# IOSEC8.net
KiCad netlist of a schematic drawn in EAGLE
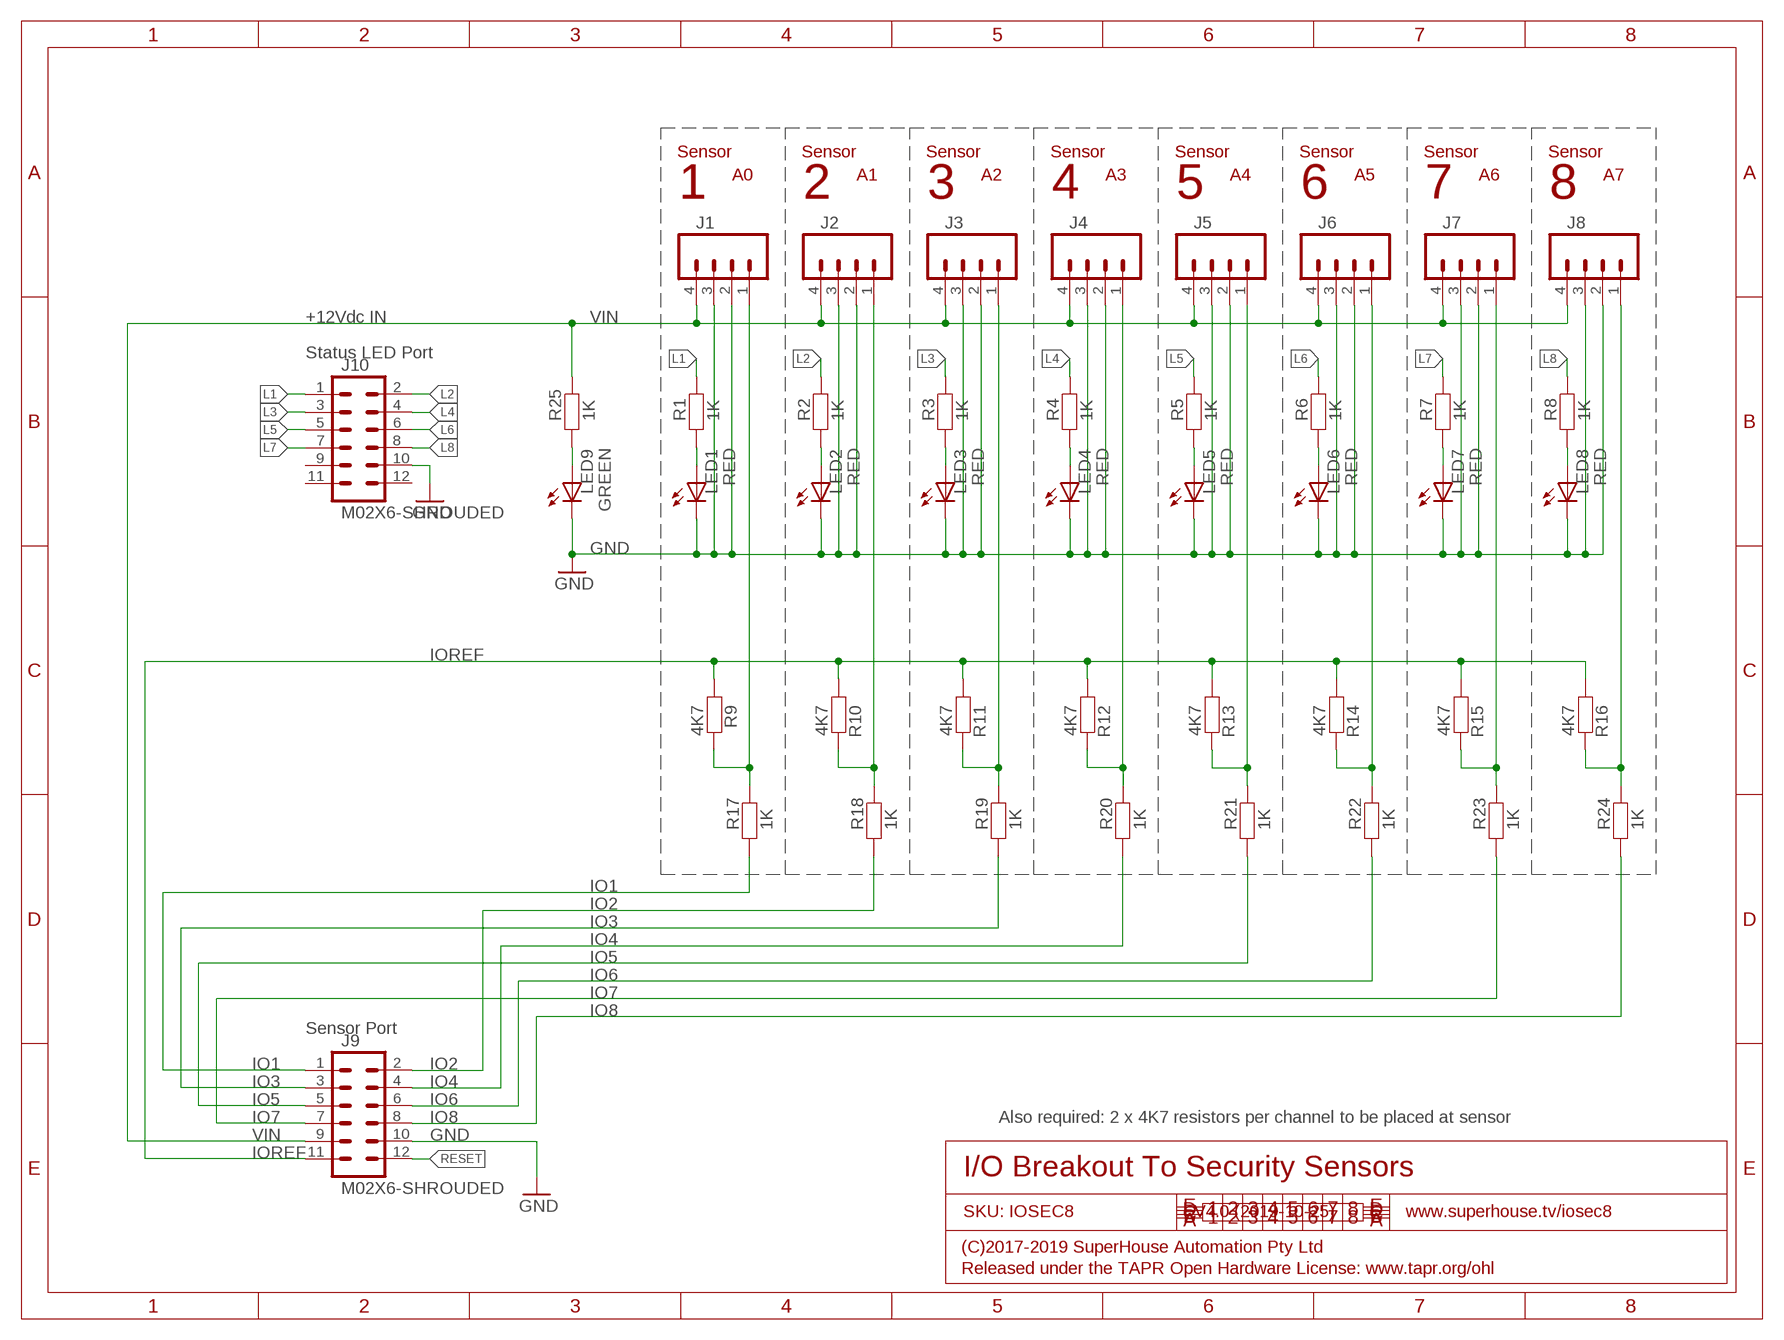
[diagram p0: schematic, sheet 1]

(export (version "E")
  (design (tool "Eeschema 10.0.6"))
  (components
    (comp (ref "J1")
      (value "M04-SCREW-3.5MM")
      (footprint "eagle-import:SCREWTERMINAL-3.5MM-4")
      (libsource (lib "eagle-import") (part "M04-SCREW-3.5MM"))
    )
    (comp (ref "J2")
      (value "M04-SCREW-3.5MM")
      (footprint "eagle-import:SCREWTERMINAL-3.5MM-4")
      (libsource (lib "eagle-import") (part "M04-SCREW-3.5MM"))
    )
    (comp (ref "J3")
      (value "M04-SCREW-3.5MM")
      (footprint "eagle-import:SCREWTERMINAL-3.5MM-4")
      (libsource (lib "eagle-import") (part "M04-SCREW-3.5MM"))
    )
    (comp (ref "J4")
      (value "M04-SCREW-3.5MM")
      (footprint "eagle-import:SCREWTERMINAL-3.5MM-4")
      (libsource (lib "eagle-import") (part "M04-SCREW-3.5MM"))
    )
    (comp (ref "J5")
      (value "M04-SCREW-3.5MM")
      (footprint "eagle-import:SCREWTERMINAL-3.5MM-4")
      (libsource (lib "eagle-import") (part "M04-SCREW-3.5MM"))
    )
    (comp (ref "J6")
      (value "M04-SCREW-3.5MM")
      (footprint "eagle-import:SCREWTERMINAL-3.5MM-4")
      (libsource (lib "eagle-import") (part "M04-SCREW-3.5MM"))
    )
    (comp (ref "J7")
      (value "M04-SCREW-3.5MM")
      (footprint "eagle-import:SCREWTERMINAL-3.5MM-4")
      (libsource (lib "eagle-import") (part "M04-SCREW-3.5MM"))
    )
    (comp (ref "J8")
      (value "M04-SCREW-3.5MM")
      (footprint "eagle-import:SCREWTERMINAL-3.5MM-4")
      (libsource (lib "eagle-import") (part "M04-SCREW-3.5MM"))
    )
    (comp (ref "J9")
      (value "M02X6-SHROUDED")
      (footprint "eagle-import:2X06-SHROUDED")
      (libsource (lib "eagle-import") (part "M02X6-SHROUDED"))
    )
    (comp (ref "J10")
      (value "M02X6-SHROUDED")
      (footprint "eagle-import:2X06-SHROUDED")
      (libsource (lib "eagle-import") (part "M02X6-SHROUDED"))
    )
    (comp (ref "LED1")
      (value "RED")
      (footprint "eagle-import:LED-0603")
      (libsource (lib "eagle-import") (part "LED0603"))
    )
    (comp (ref "LED2")
      (value "RED")
      (footprint "eagle-import:LED-0603")
      (libsource (lib "eagle-import") (part "LED0603"))
    )
    (comp (ref "LED3")
      (value "RED")
      (footprint "eagle-import:LED-0603")
      (libsource (lib "eagle-import") (part "LED0603"))
    )
    (comp (ref "LED4")
      (value "RED")
      (footprint "eagle-import:LED-0603")
      (libsource (lib "eagle-import") (part "LED0603"))
    )
    (comp (ref "LED5")
      (value "RED")
      (footprint "eagle-import:LED-0603")
      (libsource (lib "eagle-import") (part "LED0603"))
    )
    (comp (ref "LED6")
      (value "RED")
      (footprint "eagle-import:LED-0603")
      (libsource (lib "eagle-import") (part "LED0603"))
    )
    (comp (ref "LED7")
      (value "RED")
      (footprint "eagle-import:LED-0603")
      (libsource (lib "eagle-import") (part "LED0603"))
    )
    (comp (ref "LED8")
      (value "RED")
      (footprint "eagle-import:LED-0603")
      (libsource (lib "eagle-import") (part "LED0603"))
    )
    (comp (ref "LED9")
      (value "GREEN")
      (footprint "eagle-import:LED-0603")
      (libsource (lib "eagle-import") (part "LED0603"))
    )
    (comp (ref "R1")
      (value "1K")
      (footprint "eagle-import:R0603")
      (libsource (lib "eagle-import") (part "RESISTOR0603"))
    )
    (comp (ref "R2")
      (value "1K")
      (footprint "eagle-import:R0603")
      (libsource (lib "eagle-import") (part "RESISTOR0603"))
    )
    (comp (ref "R3")
      (value "1K")
      (footprint "eagle-import:R0603")
      (libsource (lib "eagle-import") (part "RESISTOR0603"))
    )
    (comp (ref "R4")
      (value "1K")
      (footprint "eagle-import:R0603")
      (libsource (lib "eagle-import") (part "RESISTOR0603"))
    )
    (comp (ref "R5")
      (value "1K")
      (footprint "eagle-import:R0603")
      (libsource (lib "eagle-import") (part "RESISTOR0603"))
    )
    (comp (ref "R6")
      (value "1K")
      (footprint "eagle-import:R0603")
      (libsource (lib "eagle-import") (part "RESISTOR0603"))
    )
    (comp (ref "R7")
      (value "1K")
      (footprint "eagle-import:R0603")
      (libsource (lib "eagle-import") (part "RESISTOR0603"))
    )
    (comp (ref "R8")
      (value "1K")
      (footprint "eagle-import:R0603")
      (libsource (lib "eagle-import") (part "RESISTOR0603"))
    )
    (comp (ref "R9")
      (value "4K7")
      (footprint "eagle-import:R0603")
      (libsource (lib "eagle-import") (part "RESISTOR0603"))
    )
    (comp (ref "R10")
      (value "4K7")
      (footprint "eagle-import:R0603")
      (libsource (lib "eagle-import") (part "RESISTOR0603"))
    )
    (comp (ref "R11")
      (value "4K7")
      (footprint "eagle-import:R0603")
      (libsource (lib "eagle-import") (part "RESISTOR0603"))
    )
    (comp (ref "R12")
      (value "4K7")
      (footprint "eagle-import:R0603")
      (libsource (lib "eagle-import") (part "RESISTOR0603"))
    )
    (comp (ref "R13")
      (value "4K7")
      (footprint "eagle-import:R0603")
      (libsource (lib "eagle-import") (part "RESISTOR0603"))
    )
    (comp (ref "R14")
      (value "4K7")
      (footprint "eagle-import:R0603")
      (libsource (lib "eagle-import") (part "RESISTOR0603"))
    )
    (comp (ref "R15")
      (value "4K7")
      (footprint "eagle-import:R0603")
      (libsource (lib "eagle-import") (part "RESISTOR0603"))
    )
    (comp (ref "R16")
      (value "4K7")
      (footprint "eagle-import:R0603")
      (libsource (lib "eagle-import") (part "RESISTOR0603"))
    )
    (comp (ref "R17")
      (value "1K")
      (footprint "eagle-import:R0603")
      (libsource (lib "eagle-import") (part "RESISTOR0603"))
    )
    (comp (ref "R18")
      (value "1K")
      (footprint "eagle-import:R0603")
      (libsource (lib "eagle-import") (part "RESISTOR0603"))
    )
    (comp (ref "R19")
      (value "1K")
      (footprint "eagle-import:R0603")
      (libsource (lib "eagle-import") (part "RESISTOR0603"))
    )
    (comp (ref "R20")
      (value "1K")
      (footprint "eagle-import:R0603")
      (libsource (lib "eagle-import") (part "RESISTOR0603"))
    )
    (comp (ref "R21")
      (value "1K")
      (footprint "eagle-import:R0603")
      (libsource (lib "eagle-import") (part "RESISTOR0603"))
    )
    (comp (ref "R22")
      (value "1K")
      (footprint "eagle-import:R0603")
      (libsource (lib "eagle-import") (part "RESISTOR0603"))
    )
    (comp (ref "R23")
      (value "1K")
      (footprint "eagle-import:R0603")
      (libsource (lib "eagle-import") (part "RESISTOR0603"))
    )
    (comp (ref "R24")
      (value "1K")
      (footprint "eagle-import:R0603")
      (libsource (lib "eagle-import") (part "RESISTOR0603"))
    )
    (comp (ref "R25")
      (value "1K")
      (footprint "eagle-import:R0603")
      (libsource (lib "eagle-import") (part "RESISTOR0603"))
    )
  )
  (nets
    (net (code "1") (name "/IO1") (class "Default")
      (node (ref "J9") (pin "1") (pinfunction "1_1") (pintype "passive"))
      (node (ref "R17") (pin "1") (pinfunction "1_1") (pintype "passive"))
    )
    (net (code "2") (name "/IO2") (class "Default")
      (node (ref "J9") (pin "2") (pinfunction "2_2") (pintype "passive"))
      (node (ref "R18") (pin "1") (pinfunction "1_1") (pintype "passive"))
    )
    (net (code "3") (name "/IO3") (class "Default")
      (node (ref "J9") (pin "3") (pinfunction "3_3") (pintype "passive"))
      (node (ref "R19") (pin "1") (pinfunction "1_1") (pintype "passive"))
    )
    (net (code "4") (name "/IO4") (class "Default")
      (node (ref "J9") (pin "4") (pinfunction "4_4") (pintype "passive"))
      (node (ref "R20") (pin "1") (pinfunction "1_1") (pintype "passive"))
    )
    (net (code "5") (name "/IO5") (class "Default")
      (node (ref "J9") (pin "5") (pinfunction "5_5") (pintype "passive"))
      (node (ref "R21") (pin "1") (pinfunction "1_1") (pintype "passive"))
    )
    (net (code "6") (name "/IO6") (class "Default")
      (node (ref "J9") (pin "6") (pinfunction "6_6") (pintype "passive"))
      (node (ref "R22") (pin "1") (pinfunction "1_1") (pintype "passive"))
    )
    (net (code "7") (name "/IO7") (class "Default")
      (node (ref "J9") (pin "7") (pinfunction "7_7") (pintype "passive"))
      (node (ref "R23") (pin "1") (pinfunction "1_1") (pintype "passive"))
    )
    (net (code "8") (name "/IO8") (class "Default")
      (node (ref "J9") (pin "8") (pinfunction "8_8") (pintype "passive"))
      (node (ref "R24") (pin "1") (pinfunction "1_1") (pintype "passive"))
    )
    (net (code "9") (name "/IOREF") (class "Default")
      (node (ref "J9") (pin "11") (pinfunction "11_11") (pintype "passive"))
      (node (ref "R10") (pin "1") (pinfunction "1_1") (pintype "passive"))
      (node (ref "R11") (pin "1") (pinfunction "1_1") (pintype "passive"))
      (node (ref "R12") (pin "1") (pinfunction "1_1") (pintype "passive"))
      (node (ref "R13") (pin "1") (pinfunction "1_1") (pintype "passive"))
      (node (ref "R14") (pin "1") (pinfunction "1_1") (pintype "passive"))
      (node (ref "R15") (pin "1") (pinfunction "1_1") (pintype "passive"))
      (node (ref "R16") (pin "1") (pinfunction "1_1") (pintype "passive"))
      (node (ref "R9") (pin "1") (pinfunction "1_1") (pintype "passive"))
    )
    (net (code "10") (name "/VIN") (class "Default")
      (node (ref "J1") (pin "4") (pinfunction "4_4") (pintype "passive"))
      (node (ref "J2") (pin "4") (pinfunction "4_4") (pintype "passive"))
      (node (ref "J3") (pin "4") (pinfunction "4_4") (pintype "passive"))
      (node (ref "J4") (pin "4") (pinfunction "4_4") (pintype "passive"))
      (node (ref "J5") (pin "4") (pinfunction "4_4") (pintype "passive"))
      (node (ref "J6") (pin "4") (pinfunction "4_4") (pintype "passive"))
      (node (ref "J7") (pin "4") (pinfunction "4_4") (pintype "passive"))
      (node (ref "J8") (pin "4") (pinfunction "4_4") (pintype "passive"))
      (node (ref "J9") (pin "9") (pinfunction "9_9") (pintype "passive"))
      (node (ref "R25") (pin "2") (pinfunction "2_2") (pintype "passive"))
    )
    (net (code "11") (name "GND") (class "Default")
      (node (ref "J1") (pin "2") (pinfunction "2_2") (pintype "passive"))
      (node (ref "J1") (pin "3") (pinfunction "3_3") (pintype "passive"))
      (node (ref "J10") (pin "10") (pinfunction "10_10") (pintype "passive"))
      (node (ref "J2") (pin "2") (pinfunction "2_2") (pintype "passive"))
      (node (ref "J2") (pin "3") (pinfunction "3_3") (pintype "passive"))
      (node (ref "J3") (pin "2") (pinfunction "2_2") (pintype "passive"))
      (node (ref "J3") (pin "3") (pinfunction "3_3") (pintype "passive"))
      (node (ref "J4") (pin "2") (pinfunction "2_2") (pintype "passive"))
      (node (ref "J4") (pin "3") (pinfunction "3_3") (pintype "passive"))
      (node (ref "J5") (pin "2") (pinfunction "2_2") (pintype "passive"))
      (node (ref "J5") (pin "3") (pinfunction "3_3") (pintype "passive"))
      (node (ref "J6") (pin "2") (pinfunction "2_2") (pintype "passive"))
      (node (ref "J6") (pin "3") (pinfunction "3_3") (pintype "passive"))
      (node (ref "J7") (pin "2") (pinfunction "2_2") (pintype "passive"))
      (node (ref "J7") (pin "3") (pinfunction "3_3") (pintype "passive"))
      (node (ref "J8") (pin "2") (pinfunction "2_2") (pintype "passive"))
      (node (ref "J8") (pin "3") (pinfunction "3_3") (pintype "passive"))
      (node (ref "J9") (pin "10") (pinfunction "10_10") (pintype "passive"))
      (node (ref "LED1") (pin "C") (pinfunction "C_C") (pintype "passive"))
      (node (ref "LED2") (pin "C") (pinfunction "C_C") (pintype "passive"))
      (node (ref "LED3") (pin "C") (pinfunction "C_C") (pintype "passive"))
      (node (ref "LED4") (pin "C") (pinfunction "C_C") (pintype "passive"))
      (node (ref "LED5") (pin "C") (pinfunction "C_C") (pintype "passive"))
      (node (ref "LED6") (pin "C") (pinfunction "C_C") (pintype "passive"))
      (node (ref "LED7") (pin "C") (pinfunction "C_C") (pintype "passive"))
      (node (ref "LED8") (pin "C") (pinfunction "C_C") (pintype "passive"))
      (node (ref "LED9") (pin "C") (pinfunction "C_C") (pintype "passive"))
    )
    (net (code "12") (name "L1") (class "Default")
      (node (ref "J10") (pin "1") (pinfunction "1_1") (pintype "passive"))
      (node (ref "R1") (pin "2") (pinfunction "2_2") (pintype "passive"))
    )
    (net (code "13") (name "L2") (class "Default")
      (node (ref "J10") (pin "2") (pinfunction "2_2") (pintype "passive"))
      (node (ref "R2") (pin "2") (pinfunction "2_2") (pintype "passive"))
    )
    (net (code "14") (name "L3") (class "Default")
      (node (ref "J10") (pin "3") (pinfunction "3_3") (pintype "passive"))
      (node (ref "R3") (pin "2") (pinfunction "2_2") (pintype "passive"))
    )
    (net (code "15") (name "L4") (class "Default")
      (node (ref "J10") (pin "4") (pinfunction "4_4") (pintype "passive"))
      (node (ref "R4") (pin "2") (pinfunction "2_2") (pintype "passive"))
    )
    (net (code "16") (name "L5") (class "Default")
      (node (ref "J10") (pin "5") (pinfunction "5_5") (pintype "passive"))
      (node (ref "R5") (pin "2") (pinfunction "2_2") (pintype "passive"))
    )
    (net (code "17") (name "L6") (class "Default")
      (node (ref "J10") (pin "6") (pinfunction "6_6") (pintype "passive"))
      (node (ref "R6") (pin "2") (pinfunction "2_2") (pintype "passive"))
    )
    (net (code "18") (name "L7") (class "Default")
      (node (ref "J10") (pin "7") (pinfunction "7_7") (pintype "passive"))
      (node (ref "R7") (pin "2") (pinfunction "2_2") (pintype "passive"))
    )
    (net (code "19") (name "L8") (class "Default")
      (node (ref "J10") (pin "8") (pinfunction "8_8") (pintype "passive"))
      (node (ref "R8") (pin "2") (pinfunction "2_2") (pintype "passive"))
    )
    (net (code "20") (name "Net-(J1-Pad1)") (class "Default")
      (node (ref "J1") (pin "1") (pinfunction "1_1") (pintype "passive"))
      (node (ref "R17") (pin "2") (pinfunction "2_2") (pintype "passive"))
      (node (ref "R9") (pin "2") (pinfunction "2_2") (pintype "passive"))
    )
    (net (code "21") (name "Net-(J2-Pad1)") (class "Default")
      (node (ref "J2") (pin "1") (pinfunction "1_1") (pintype "passive"))
      (node (ref "R10") (pin "2") (pinfunction "2_2") (pintype "passive"))
      (node (ref "R18") (pin "2") (pinfunction "2_2") (pintype "passive"))
    )
    (net (code "22") (name "Net-(J3-Pad1)") (class "Default")
      (node (ref "J3") (pin "1") (pinfunction "1_1") (pintype "passive"))
      (node (ref "R11") (pin "2") (pinfunction "2_2") (pintype "passive"))
      (node (ref "R19") (pin "2") (pinfunction "2_2") (pintype "passive"))
    )
    (net (code "23") (name "Net-(J4-Pad1)") (class "Default")
      (node (ref "J4") (pin "1") (pinfunction "1_1") (pintype "passive"))
      (node (ref "R12") (pin "2") (pinfunction "2_2") (pintype "passive"))
      (node (ref "R20") (pin "2") (pinfunction "2_2") (pintype "passive"))
    )
    (net (code "24") (name "Net-(J5-Pad1)") (class "Default")
      (node (ref "J5") (pin "1") (pinfunction "1_1") (pintype "passive"))
      (node (ref "R13") (pin "2") (pinfunction "2_2") (pintype "passive"))
      (node (ref "R21") (pin "2") (pinfunction "2_2") (pintype "passive"))
    )
    (net (code "25") (name "Net-(J6-Pad1)") (class "Default")
      (node (ref "J6") (pin "1") (pinfunction "1_1") (pintype "passive"))
      (node (ref "R14") (pin "2") (pinfunction "2_2") (pintype "passive"))
      (node (ref "R22") (pin "2") (pinfunction "2_2") (pintype "passive"))
    )
    (net (code "26") (name "Net-(J7-Pad1)") (class "Default")
      (node (ref "J7") (pin "1") (pinfunction "1_1") (pintype "passive"))
      (node (ref "R15") (pin "2") (pinfunction "2_2") (pintype "passive"))
      (node (ref "R23") (pin "2") (pinfunction "2_2") (pintype "passive"))
    )
    (net (code "27") (name "Net-(J8-Pad1)") (class "Default")
      (node (ref "J8") (pin "1") (pinfunction "1_1") (pintype "passive"))
      (node (ref "R16") (pin "2") (pinfunction "2_2") (pintype "passive"))
      (node (ref "R24") (pin "2") (pinfunction "2_2") (pintype "passive"))
    )
    (net (code "28") (name "Net-(LED1-PadA)") (class "Default")
      (node (ref "LED1") (pin "A") (pinfunction "A_A") (pintype "passive"))
      (node (ref "R1") (pin "1") (pinfunction "1_1") (pintype "passive"))
    )
    (net (code "29") (name "Net-(LED2-PadA)") (class "Default")
      (node (ref "LED2") (pin "A") (pinfunction "A_A") (pintype "passive"))
      (node (ref "R2") (pin "1") (pinfunction "1_1") (pintype "passive"))
    )
    (net (code "30") (name "Net-(LED3-PadA)") (class "Default")
      (node (ref "LED3") (pin "A") (pinfunction "A_A") (pintype "passive"))
      (node (ref "R3") (pin "1") (pinfunction "1_1") (pintype "passive"))
    )
    (net (code "31") (name "Net-(LED4-PadA)") (class "Default")
      (node (ref "LED4") (pin "A") (pinfunction "A_A") (pintype "passive"))
      (node (ref "R4") (pin "1") (pinfunction "1_1") (pintype "passive"))
    )
    (net (code "32") (name "Net-(LED5-PadA)") (class "Default")
      (node (ref "LED5") (pin "A") (pinfunction "A_A") (pintype "passive"))
      (node (ref "R5") (pin "1") (pinfunction "1_1") (pintype "passive"))
    )
    (net (code "33") (name "Net-(LED6-PadA)") (class "Default")
      (node (ref "LED6") (pin "A") (pinfunction "A_A") (pintype "passive"))
      (node (ref "R6") (pin "1") (pinfunction "1_1") (pintype "passive"))
    )
    (net (code "34") (name "Net-(LED7-PadA)") (class "Default")
      (node (ref "LED7") (pin "A") (pinfunction "A_A") (pintype "passive"))
      (node (ref "R7") (pin "1") (pinfunction "1_1") (pintype "passive"))
    )
    (net (code "35") (name "Net-(LED8-PadA)") (class "Default")
      (node (ref "LED8") (pin "A") (pinfunction "A_A") (pintype "passive"))
      (node (ref "R8") (pin "1") (pinfunction "1_1") (pintype "passive"))
    )
    (net (code "36") (name "Net-(LED9-PadA)") (class "Default")
      (node (ref "LED9") (pin "A") (pinfunction "A_A") (pintype "passive"))
      (node (ref "R25") (pin "1") (pinfunction "1_1") (pintype "passive"))
    )
    (net (code "37") (name "RESET") (class "Default")
      (node (ref "J9") (pin "12") (pinfunction "12_12") (pintype "passive"))
    )
    (net (code "38") (name "unconnected-(J10-Pad9)") (class "Default")
      (node (ref "J10") (pin "9") (pinfunction "9_9") (pintype "passive"))
    )
    (net (code "39") (name "unconnected-(J10-Pad11)") (class "Default")
      (node (ref "J10") (pin "11") (pinfunction "11_11") (pintype "passive"))
    )
    (net (code "40") (name "unconnected-(J10-Pad12)") (class "Default")
      (node (ref "J10") (pin "12") (pinfunction "12_12") (pintype "passive"))
    )
  )
)
